# TIshematic_1.net
KiCad netlist of a schematic drawn in EAGLE
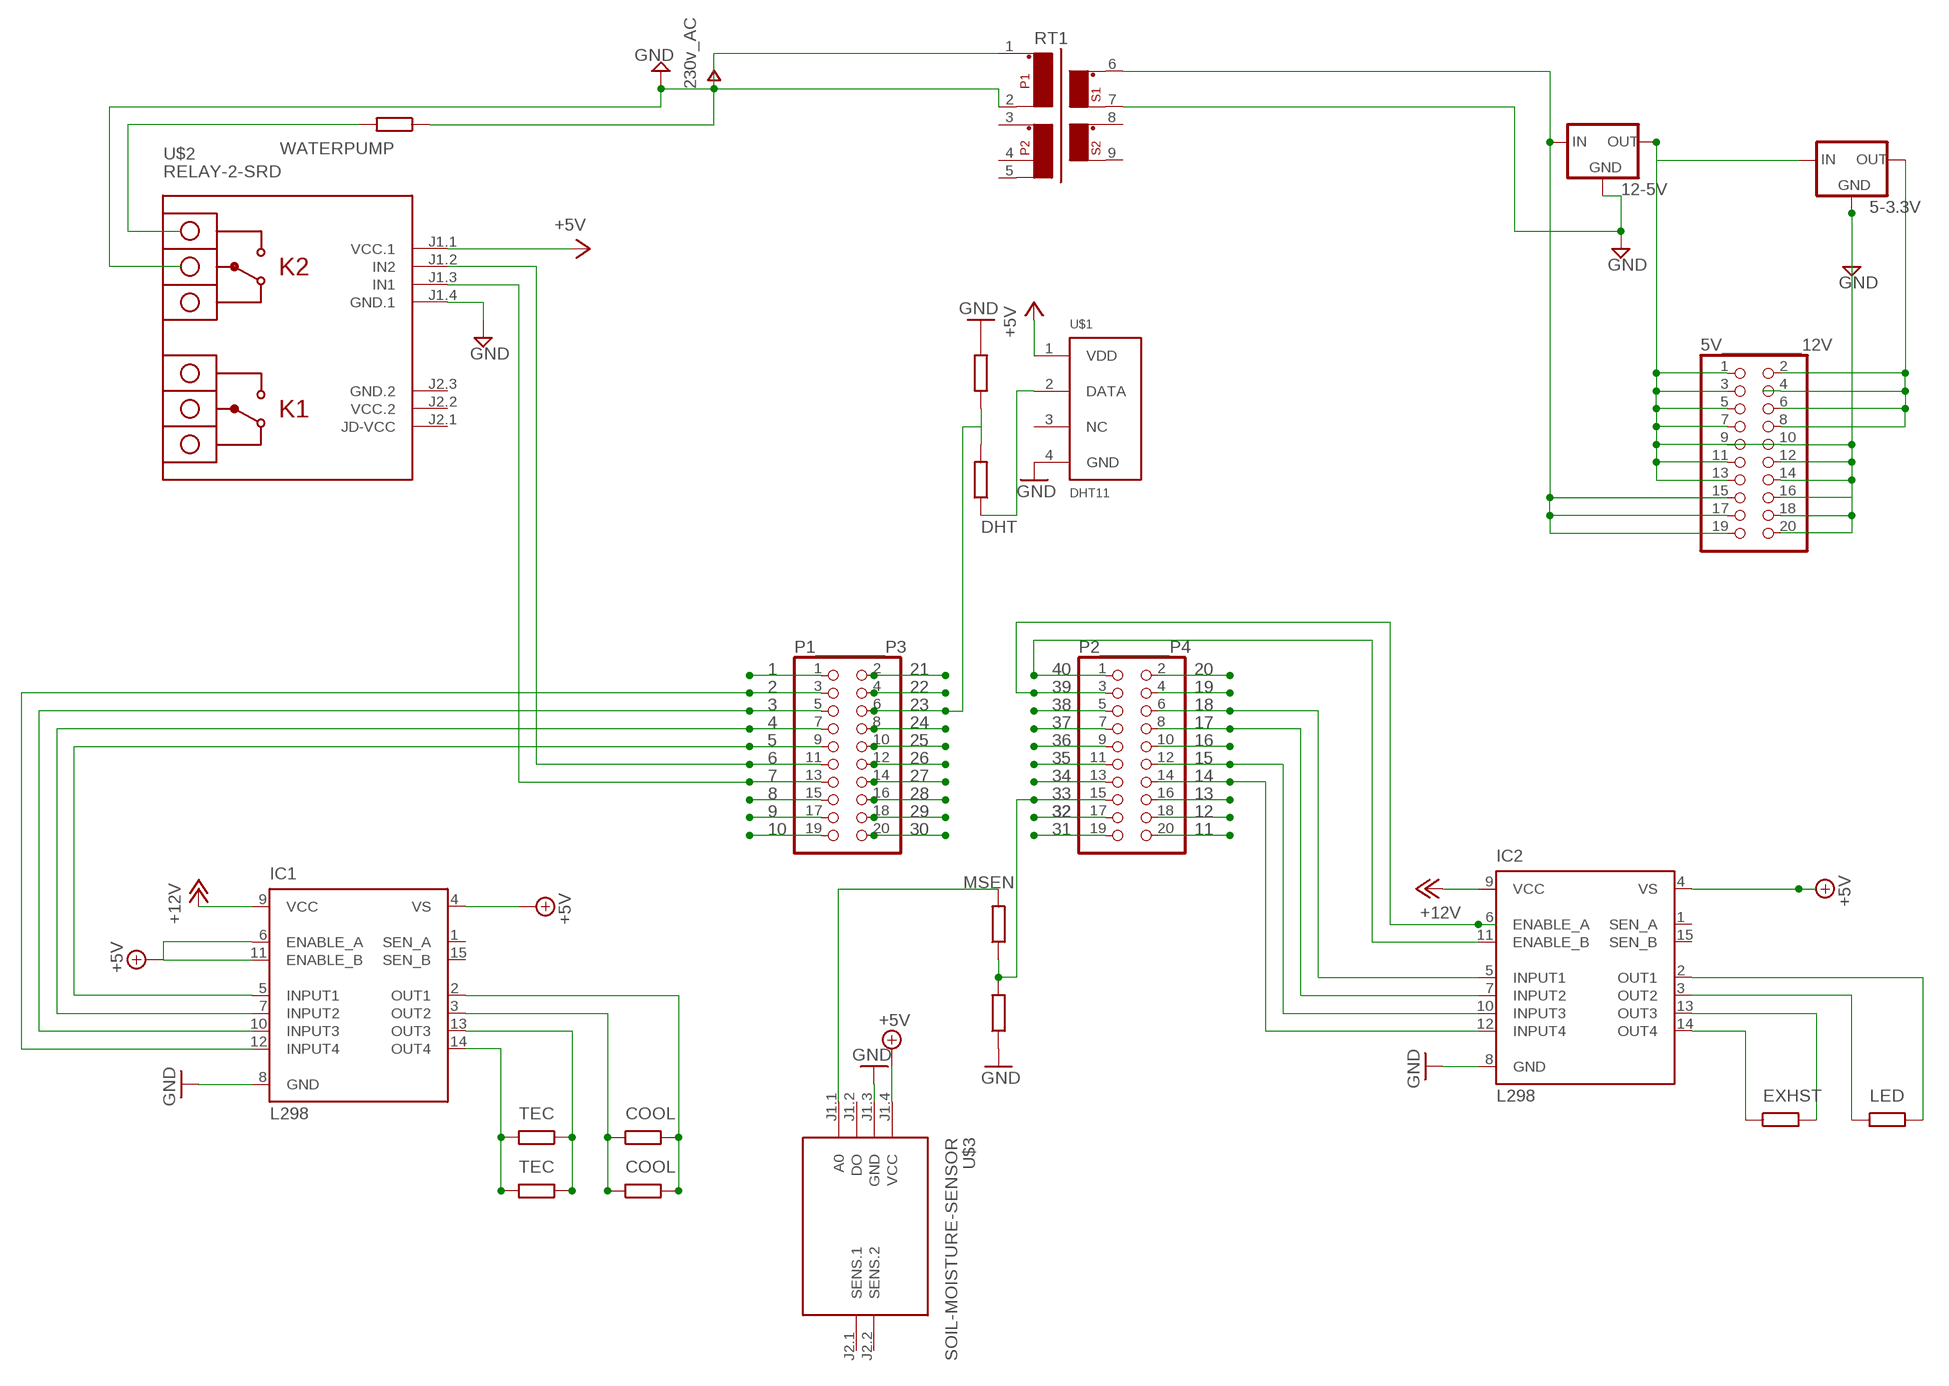
[diagram p0: schematic, sheet 1]

(export (version "E")
  (design (tool "Eeschema 10.0.6"))
  (components
    (comp (ref "5-3.3V")
      (value "78XXL")
      (footprint "eagle-import:78XXL")
      (libsource (lib "eagle-import") (part "78XXL"))
    )
    (comp (ref "5V________12V")
      (value "PINHD-2X10")
      (footprint "eagle-import:2X10")
      (libsource (lib "eagle-import") (part "PINHD-2X10"))
    )
    (comp (ref "12-5V")
      (value "78XXL")
      (footprint "eagle-import:78XXL")
      (libsource (lib "eagle-import") (part "78XXL"))
    )
    (comp (ref "IC1")
      (value "L298")
      (footprint "eagle-import:MULTIWATT-15")
      (fields (field (name "MPN") "L298N"))
      (libsource (lib "eagle-import") (part "L298"))
    )
    (comp (ref "IC2")
      (value "L298")
      (footprint "eagle-import:MULTIWATT-15")
      (fields (field (name "MPN") "L298N"))
      (libsource (lib "eagle-import") (part "L298"))
    )
    (comp (ref "P1_______P3")
      (value "PINHD-2X10")
      (footprint "eagle-import:2X10")
      (libsource (lib "eagle-import") (part "PINHD-2X10"))
    )
    (comp (ref "P2_______P4")
      (value "PINHD-2X10")
      (footprint "eagle-import:2X10")
      (libsource (lib "eagle-import") (part "PINHD-2X10"))
    )
    (comp (ref "RT1")
      (value "15VA")
      (footprint "eagle-import:15VA")
      (libsource (lib "eagle-import") (part "15VA"))
    )
    (comp (ref "U$1")
      (value "DHT11")
      (footprint "eagle-import:DHT11")
      (libsource (lib "eagle-import") (part "DHT11"))
    )
    (comp (ref "U$2")
      (value "RELAY-2-SRD")
      (footprint "eagle-import:RELAY-2-SRD")
      (libsource (lib "eagle-import") (part "RELAY-2-SRD"))
    )
    (comp (ref "U$3")
      (value "SOIL-MOISTURE-SENSOR")
      (footprint "eagle-import:SOIL-MOISTURE-SENSOR")
      (libsource (lib "eagle-import") (part "SOIL-MOISTURE-SENSOR"))
    )
  )
  (nets
    (net (code "1") (name "+5V") (class "Default")
      (node (ref "IC1") (pin "11") (pinfunction "ENABLE_B_11") (pintype "input"))
      (node (ref "IC1") (pin "4") (pinfunction "VS_4") (pintype "power_in"))
      (node (ref "IC1") (pin "6") (pinfunction "ENABLE_A_6") (pintype "input"))
      (node (ref "IC2") (pin "4") (pinfunction "VS_4") (pintype "power_in"))
      (node (ref "U$1") (pin "1") (pinfunction "VDD_1") (pintype "power_in"))
      (node (ref "U$2") (pin "J1.1") (pinfunction "VCC.1_J1.1") (pintype "power_in"))
      (node (ref "U$3") (pin "J1.4") (pinfunction "VCC_J1.4") (pintype "power_in"))
    )
    (net (code "2") (name "+12V") (class "Default")
      (node (ref "IC1") (pin "9") (pinfunction "VCC_9") (pintype "power_in"))
      (node (ref "IC2") (pin "9") (pinfunction "VCC_9") (pintype "power_in"))
    )
    (net (code "3") (name "/2") (class "Default")
      (node (ref "IC2") (pin "5") (pinfunction "INPUT1_5") (pintype "input"))
      (node (ref "IC2") (pin "7") (pinfunction "INPUT2_7") (pintype "input"))
      (node (ref "P1_______P3") (pin "1") (pinfunction "1_1") (pintype "passive"))
      (node (ref "P1_______P3") (pin "10") (pinfunction "10_10") (pintype "passive"))
      (node (ref "P1_______P3") (pin "11") (pinfunction "11_11") (pintype "passive"))
      (node (ref "P1_______P3") (pin "12") (pinfunction "12_12") (pintype "passive"))
      (node (ref "P1_______P3") (pin "13") (pinfunction "13_13") (pintype "passive"))
      (node (ref "P1_______P3") (pin "14") (pinfunction "14_14") (pintype "passive"))
      (node (ref "P1_______P3") (pin "15") (pinfunction "15_15") (pintype "passive"))
      (node (ref "P1_______P3") (pin "16") (pinfunction "16_16") (pintype "passive"))
      (node (ref "P1_______P3") (pin "17") (pinfunction "17_17") (pintype "passive"))
      (node (ref "P1_______P3") (pin "18") (pinfunction "18_18") (pintype "passive"))
      (node (ref "P1_______P3") (pin "19") (pinfunction "19_19") (pintype "passive"))
      (node (ref "P1_______P3") (pin "2") (pinfunction "2_2") (pintype "passive"))
      (node (ref "P1_______P3") (pin "20") (pinfunction "20_20") (pintype "passive"))
      (node (ref "P1_______P3") (pin "4") (pinfunction "4_4") (pintype "passive"))
      (node (ref "P1_______P3") (pin "8") (pinfunction "8_8") (pintype "passive"))
      (node (ref "P2_______P4") (pin "10") (pinfunction "10_10") (pintype "passive"))
      (node (ref "P2_______P4") (pin "11") (pinfunction "11_11") (pintype "passive"))
      (node (ref "P2_______P4") (pin "13") (pinfunction "13_13") (pintype "passive"))
      (node (ref "P2_______P4") (pin "15") (pinfunction "15_15") (pintype "passive"))
      (node (ref "P2_______P4") (pin "16") (pinfunction "16_16") (pintype "passive"))
      (node (ref "P2_______P4") (pin "17") (pinfunction "17_17") (pintype "passive"))
      (node (ref "P2_______P4") (pin "18") (pinfunction "18_18") (pintype "passive"))
      (node (ref "P2_______P4") (pin "19") (pinfunction "19_19") (pintype "passive"))
      (node (ref "P2_______P4") (pin "2") (pinfunction "2_2") (pintype "passive"))
      (node (ref "P2_______P4") (pin "20") (pinfunction "20_20") (pintype "passive"))
      (node (ref "P2_______P4") (pin "5") (pinfunction "5_5") (pintype "passive"))
      (node (ref "P2_______P4") (pin "6") (pinfunction "6_6") (pintype "passive"))
      (node (ref "P2_______P4") (pin "7") (pinfunction "7_7") (pintype "passive"))
      (node (ref "P2_______P4") (pin "8") (pinfunction "8_8") (pintype "passive"))
      (node (ref "P2_______P4") (pin "9") (pinfunction "9_9") (pintype "passive"))
      (node (ref "U$2") (pin "J1.2") (pinfunction "IN2_J1.2") (pintype "bidirectional"))
      (node (ref "U$2") (pin "J1.3") (pinfunction "IN1_J1.3") (pintype "bidirectional"))
    )
    (net (code "4") (name "/40") (class "Default")
      (node (ref "IC2") (pin "11") (pinfunction "ENABLE_B_11") (pintype "input"))
      (node (ref "P2_______P4") (pin "1") (pinfunction "1_1") (pintype "passive"))
    )
    (net (code "5") (name "/COOL") (class "Default")
      (node (ref "IC1") (pin "3") (pinfunction "OUT2_3") (pintype "output"))
    )
    (net (code "6") (name "/DHT") (class "Default")
      (node (ref "P1_______P3") (pin "6") (pinfunction "6_6") (pintype "passive"))
    )
    (net (code "7") (name "/EXHST") (class "Default")
      (node (ref "IC2") (pin "14") (pinfunction "OUT4_14") (pintype "output"))
    )
    (net (code "8") (name "/GND.2") (class "Default")
      (node (ref "U$2") (pin "J2.3") (pinfunction "GND.2_J2.3") (pintype "power_in"))
    )
    (net (code "9") (name "/LED") (class "Default")
      (node (ref "IC2") (pin "3") (pinfunction "OUT2_3") (pintype "output"))
    )
    (net (code "10") (name "/MSEN") (class "Default")
      (node (ref "U$3") (pin "J1.1") (pinfunction "A0_J1.1") (pintype "bidirectional"))
    )
    (net (code "11") (name "/TEC") (class "Default")
      (node (ref "IC1") (pin "14") (pinfunction "OUT4_14") (pintype "output"))
    )
    (net (code "12") (name "/VCC.2") (class "Default")
      (node (ref "U$2") (pin "J2.2") (pinfunction "VCC.2_J2.2") (pintype "power_in"))
    )
    (net (code "14") (name "230v_AC") (class "Default")
      (node (ref "12-5V") (pin "GND") (pinfunction "GND_GND") (pintype "input"))
      (node (ref "5-3.3V") (pin "GND") (pinfunction "GND_GND") (pintype "input"))
      (node (ref "5V________12V") (pin "10") (pinfunction "10_10") (pintype "passive"))
      (node (ref "5V________12V") (pin "12") (pinfunction "12_12") (pintype "passive"))
      (node (ref "5V________12V") (pin "14") (pinfunction "14_14") (pintype "passive"))
      (node (ref "5V________12V") (pin "16") (pinfunction "16_16") (pintype "passive"))
      (node (ref "5V________12V") (pin "18") (pinfunction "18_18") (pintype "passive"))
      (node (ref "5V________12V") (pin "20") (pinfunction "20_20") (pintype "passive"))
      (node (ref "IC1") (pin "8") (pinfunction "GND_8") (pintype "power_in"))
      (node (ref "IC2") (pin "8") (pinfunction "GND_8") (pintype "power_in"))
      (node (ref "RT1") (pin "1") (pinfunction "1_1") (pintype "passive"))
      (node (ref "RT1") (pin "2") (pinfunction "2_2") (pintype "passive"))
      (node (ref "RT1") (pin "7") (pinfunction "7_7") (pintype "passive"))
      (node (ref "U$1") (pin "4") (pinfunction "GND_4") (pintype "power_in"))
      (node (ref "U$2") (pin "J1.4") (pinfunction "GND.1_J1.4") (pintype "power_in"))
      (node (ref "U$3") (pin "J1.3") (pinfunction "GND_J1.3") (pintype "power_in"))
    )
    (net (code "15") (name "Net-(5-3.3V-PadOUT)") (class "Default")
      (node (ref "5-3.3V") (pin "OUT") (pinfunction "OUT_OUT") (pintype "passive"))
      (node (ref "5V________12V") (pin "2") (pinfunction "2_2") (pintype "passive"))
      (node (ref "5V________12V") (pin "4") (pinfunction "4_4") (pintype "passive"))
      (node (ref "5V________12V") (pin "6") (pinfunction "6_6") (pintype "passive"))
      (node (ref "5V________12V") (pin "8") (pinfunction "8_8") (pintype "passive"))
    )
    (net (code "16") (name "Net-(12-5V-PadIN)") (class "Default")
      (node (ref "12-5V") (pin "IN") (pinfunction "IN_IN") (pintype "input"))
      (node (ref "5V________12V") (pin "15") (pinfunction "15_15") (pintype "passive"))
      (node (ref "5V________12V") (pin "17") (pinfunction "17_17") (pintype "passive"))
      (node (ref "5V________12V") (pin "19") (pinfunction "19_19") (pintype "passive"))
      (node (ref "RT1") (pin "6") (pinfunction "6_6") (pintype "passive"))
    )
    (net (code "17") (name "Net-(12-5V-PadOUT)") (class "Default")
      (node (ref "12-5V") (pin "OUT") (pinfunction "OUT_OUT") (pintype "passive"))
      (node (ref "5-3.3V") (pin "IN") (pinfunction "IN_IN") (pintype "input"))
      (node (ref "5V________12V") (pin "1") (pinfunction "1_1") (pintype "passive"))
      (node (ref "5V________12V") (pin "11") (pinfunction "11_11") (pintype "passive"))
      (node (ref "5V________12V") (pin "13") (pinfunction "13_13") (pintype "passive"))
      (node (ref "5V________12V") (pin "3") (pinfunction "3_3") (pintype "passive"))
      (node (ref "5V________12V") (pin "5") (pinfunction "5_5") (pintype "passive"))
      (node (ref "5V________12V") (pin "7") (pinfunction "7_7") (pintype "passive"))
      (node (ref "5V________12V") (pin "9") (pinfunction "9_9") (pintype "passive"))
    )
    (net (code "18") (name "Net-(IC1-INPUT1)") (class "Default")
      (node (ref "IC1") (pin "5") (pinfunction "INPUT1_5") (pintype "input"))
      (node (ref "P1_______P3") (pin "9") (pinfunction "9_9") (pintype "passive"))
    )
    (net (code "19") (name "Net-(IC1-INPUT2)") (class "Default")
      (node (ref "IC1") (pin "7") (pinfunction "INPUT2_7") (pintype "input"))
      (node (ref "P1_______P3") (pin "7") (pinfunction "7_7") (pintype "passive"))
    )
    (net (code "20") (name "Net-(IC1-INPUT3)") (class "Default")
      (node (ref "IC1") (pin "10") (pinfunction "INPUT3_10") (pintype "input"))
      (node (ref "P1_______P3") (pin "5") (pinfunction "5_5") (pintype "passive"))
    )
    (net (code "21") (name "Net-(IC1-INPUT4)") (class "Default")
      (node (ref "IC1") (pin "12") (pinfunction "INPUT4_12") (pintype "input"))
      (node (ref "P1_______P3") (pin "3") (pinfunction "3_3") (pintype "passive"))
    )
    (net (code "22") (name "Net-(IC2-ENABLE_A)") (class "Default")
      (node (ref "IC2") (pin "6") (pinfunction "ENABLE_A_6") (pintype "input"))
      (node (ref "P2_______P4") (pin "3") (pinfunction "3_3") (pintype "passive"))
    )
    (net (code "23") (name "Net-(IC2-INPUT3)") (class "Default")
      (node (ref "IC2") (pin "10") (pinfunction "INPUT3_10") (pintype "input"))
      (node (ref "P2_______P4") (pin "12") (pinfunction "12_12") (pintype "passive"))
    )
    (net (code "24") (name "Net-(IC2-INPUT4)") (class "Default")
      (node (ref "IC2") (pin "12") (pinfunction "INPUT4_12") (pintype "input"))
      (node (ref "P2_______P4") (pin "14") (pinfunction "14_14") (pintype "passive"))
    )
    (net (code "25") (name "unconnected-(IC1-OUT1-Pad2)") (class "Default")
      (node (ref "IC1") (pin "2") (pinfunction "OUT1_2") (pintype "output"))
    )
    (net (code "26") (name "unconnected-(IC1-OUT3-Pad13)") (class "Default")
      (node (ref "IC1") (pin "13") (pinfunction "OUT3_13") (pintype "output"))
    )
    (net (code "27") (name "unconnected-(IC1-SEN_A-Pad1)") (class "Default")
      (node (ref "IC1") (pin "1") (pinfunction "SEN_A_1") (pintype "input"))
    )
    (net (code "28") (name "unconnected-(IC1-SEN_B-Pad15)") (class "Default")
      (node (ref "IC1") (pin "15") (pinfunction "SEN_B_15") (pintype "input"))
    )
    (net (code "29") (name "unconnected-(IC2-OUT1-Pad2)") (class "Default")
      (node (ref "IC2") (pin "2") (pinfunction "OUT1_2") (pintype "output"))
    )
    (net (code "30") (name "unconnected-(IC2-OUT3-Pad13)") (class "Default")
      (node (ref "IC2") (pin "13") (pinfunction "OUT3_13") (pintype "output"))
    )
    (net (code "31") (name "unconnected-(IC2-SEN_A-Pad1)") (class "Default")
      (node (ref "IC2") (pin "1") (pinfunction "SEN_A_1") (pintype "input"))
    )
    (net (code "32") (name "unconnected-(IC2-SEN_B-Pad15)") (class "Default")
      (node (ref "IC2") (pin "15") (pinfunction "SEN_B_15") (pintype "input"))
    )
    (net (code "33") (name "unconnected-(P2_______P4-Pad4)") (class "Default")
      (node (ref "P2_______P4") (pin "4") (pinfunction "4_4") (pintype "passive"))
    )
    (net (code "34") (name "unconnected-(RT1-Pad3)") (class "Default")
      (node (ref "RT1") (pin "3") (pinfunction "3_3") (pintype "passive"))
    )
    (net (code "35") (name "unconnected-(RT1-Pad4)") (class "Default")
      (node (ref "RT1") (pin "4") (pinfunction "4_4") (pintype "passive"))
    )
    (net (code "36") (name "unconnected-(RT1-Pad5)") (class "Default")
      (node (ref "RT1") (pin "5") (pinfunction "5_5") (pintype "passive"))
    )
    (net (code "37") (name "unconnected-(RT1-Pad8)") (class "Default")
      (node (ref "RT1") (pin "8") (pinfunction "8_8") (pintype "passive"))
    )
    (net (code "38") (name "unconnected-(RT1-Pad9)") (class "Default")
      (node (ref "RT1") (pin "9") (pinfunction "9_9") (pintype "passive"))
    )
    (net (code "39") (name "unconnected-(U$1-DATA-Pad2)") (class "Default")
      (node (ref "U$1") (pin "2") (pinfunction "DATA_2") (pintype "bidirectional"))
    )
    (net (code "40") (name "unconnected-(U$1-NC-Pad3)") (class "Default")
      (node (ref "U$1") (pin "3") (pinfunction "NC_3") (pintype "bidirectional"))
    )
    (net (code "41") (name "unconnected-(U$2-JD-VCC-PadJ2.1)") (class "Default")
      (node (ref "U$2") (pin "J2.1") (pinfunction "JD-VCC_J2.1") (pintype "bidirectional"))
    )
    (net (code "42") (name "unconnected-(U$3-DO-PadJ1.2)") (class "Default")
      (node (ref "U$3") (pin "J1.2") (pinfunction "DO_J1.2") (pintype "output"))
    )
    (net (code "43") (name "unconnected-(U$3-SENS.1-PadJ2.1)") (class "Default")
      (node (ref "U$3") (pin "J2.1") (pinfunction "SENS.1_J2.1") (pintype "bidirectional"))
    )
    (net (code "44") (name "unconnected-(U$3-SENS.2-PadJ2.2)") (class "Default")
      (node (ref "U$3") (pin "J2.2") (pinfunction "SENS.2_J2.2") (pintype "bidirectional"))
    )
  )
)
